# UARTAI.net
KiCad netlist of a schematic drawn in EasyEDA Pro
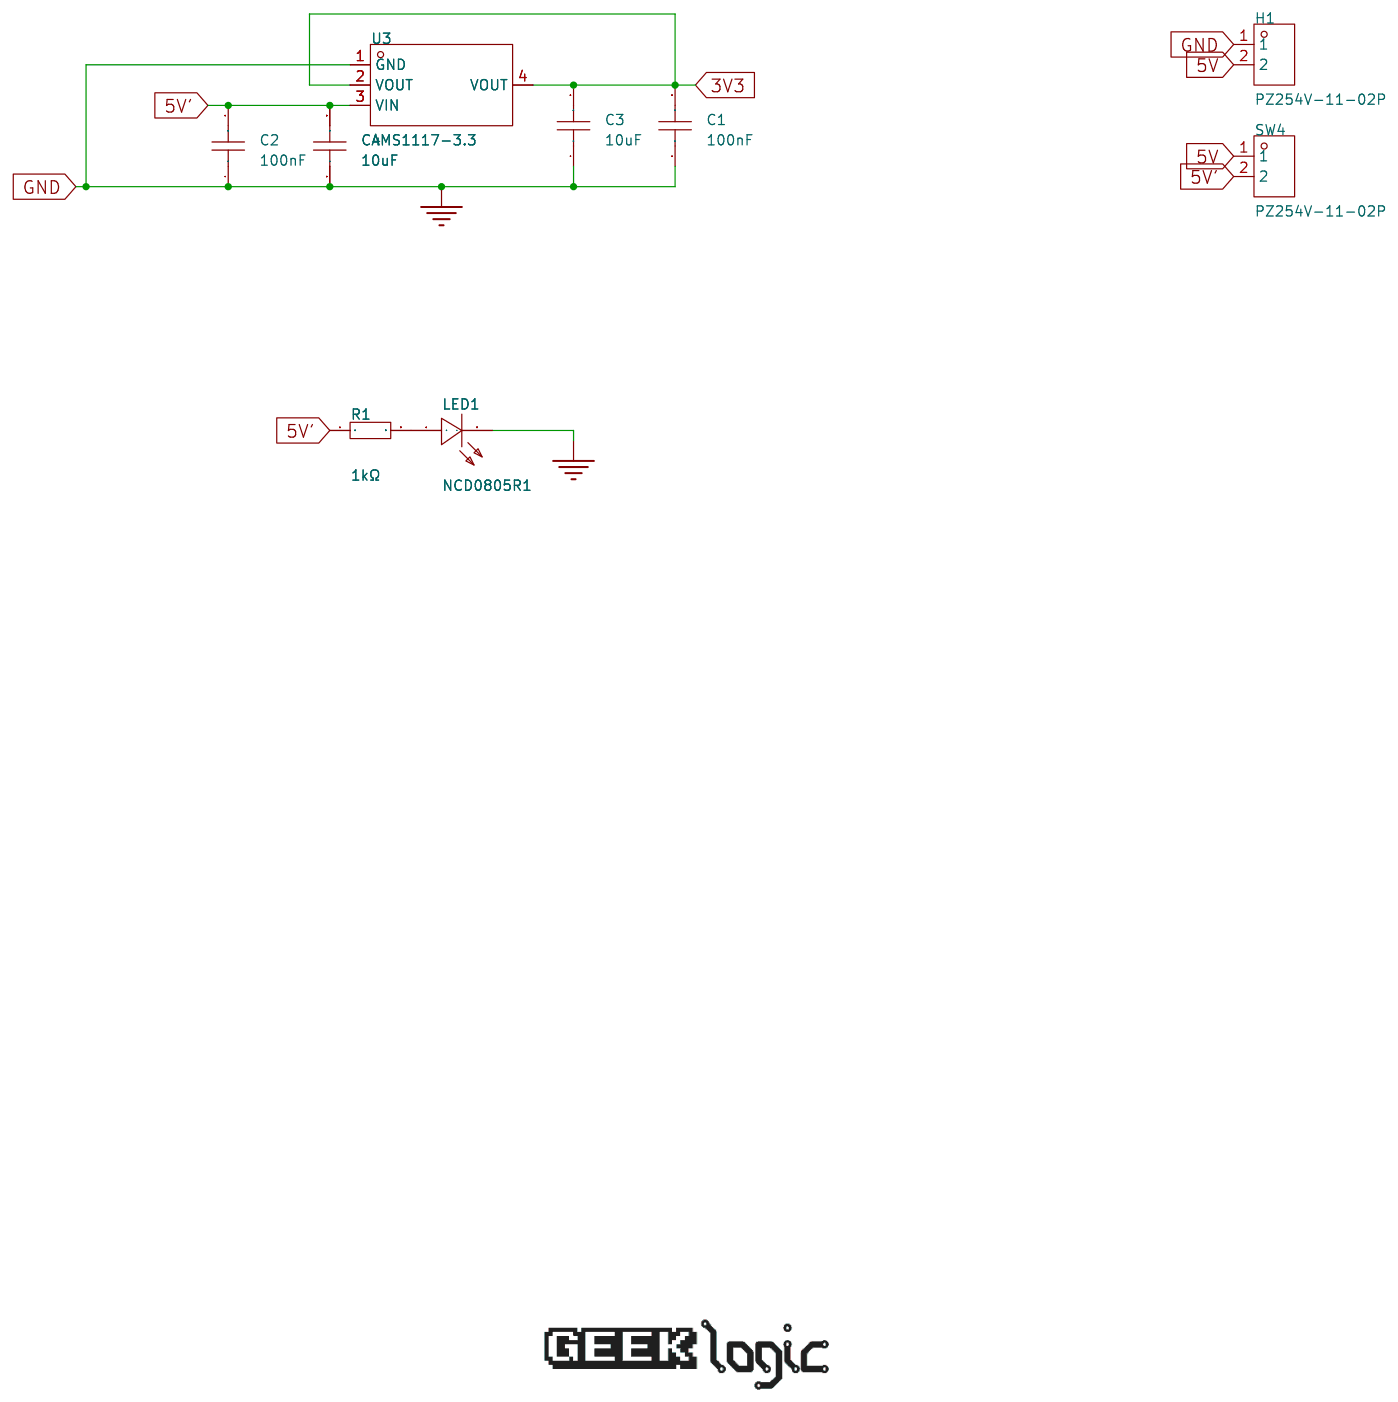
[diagram p0: Power]
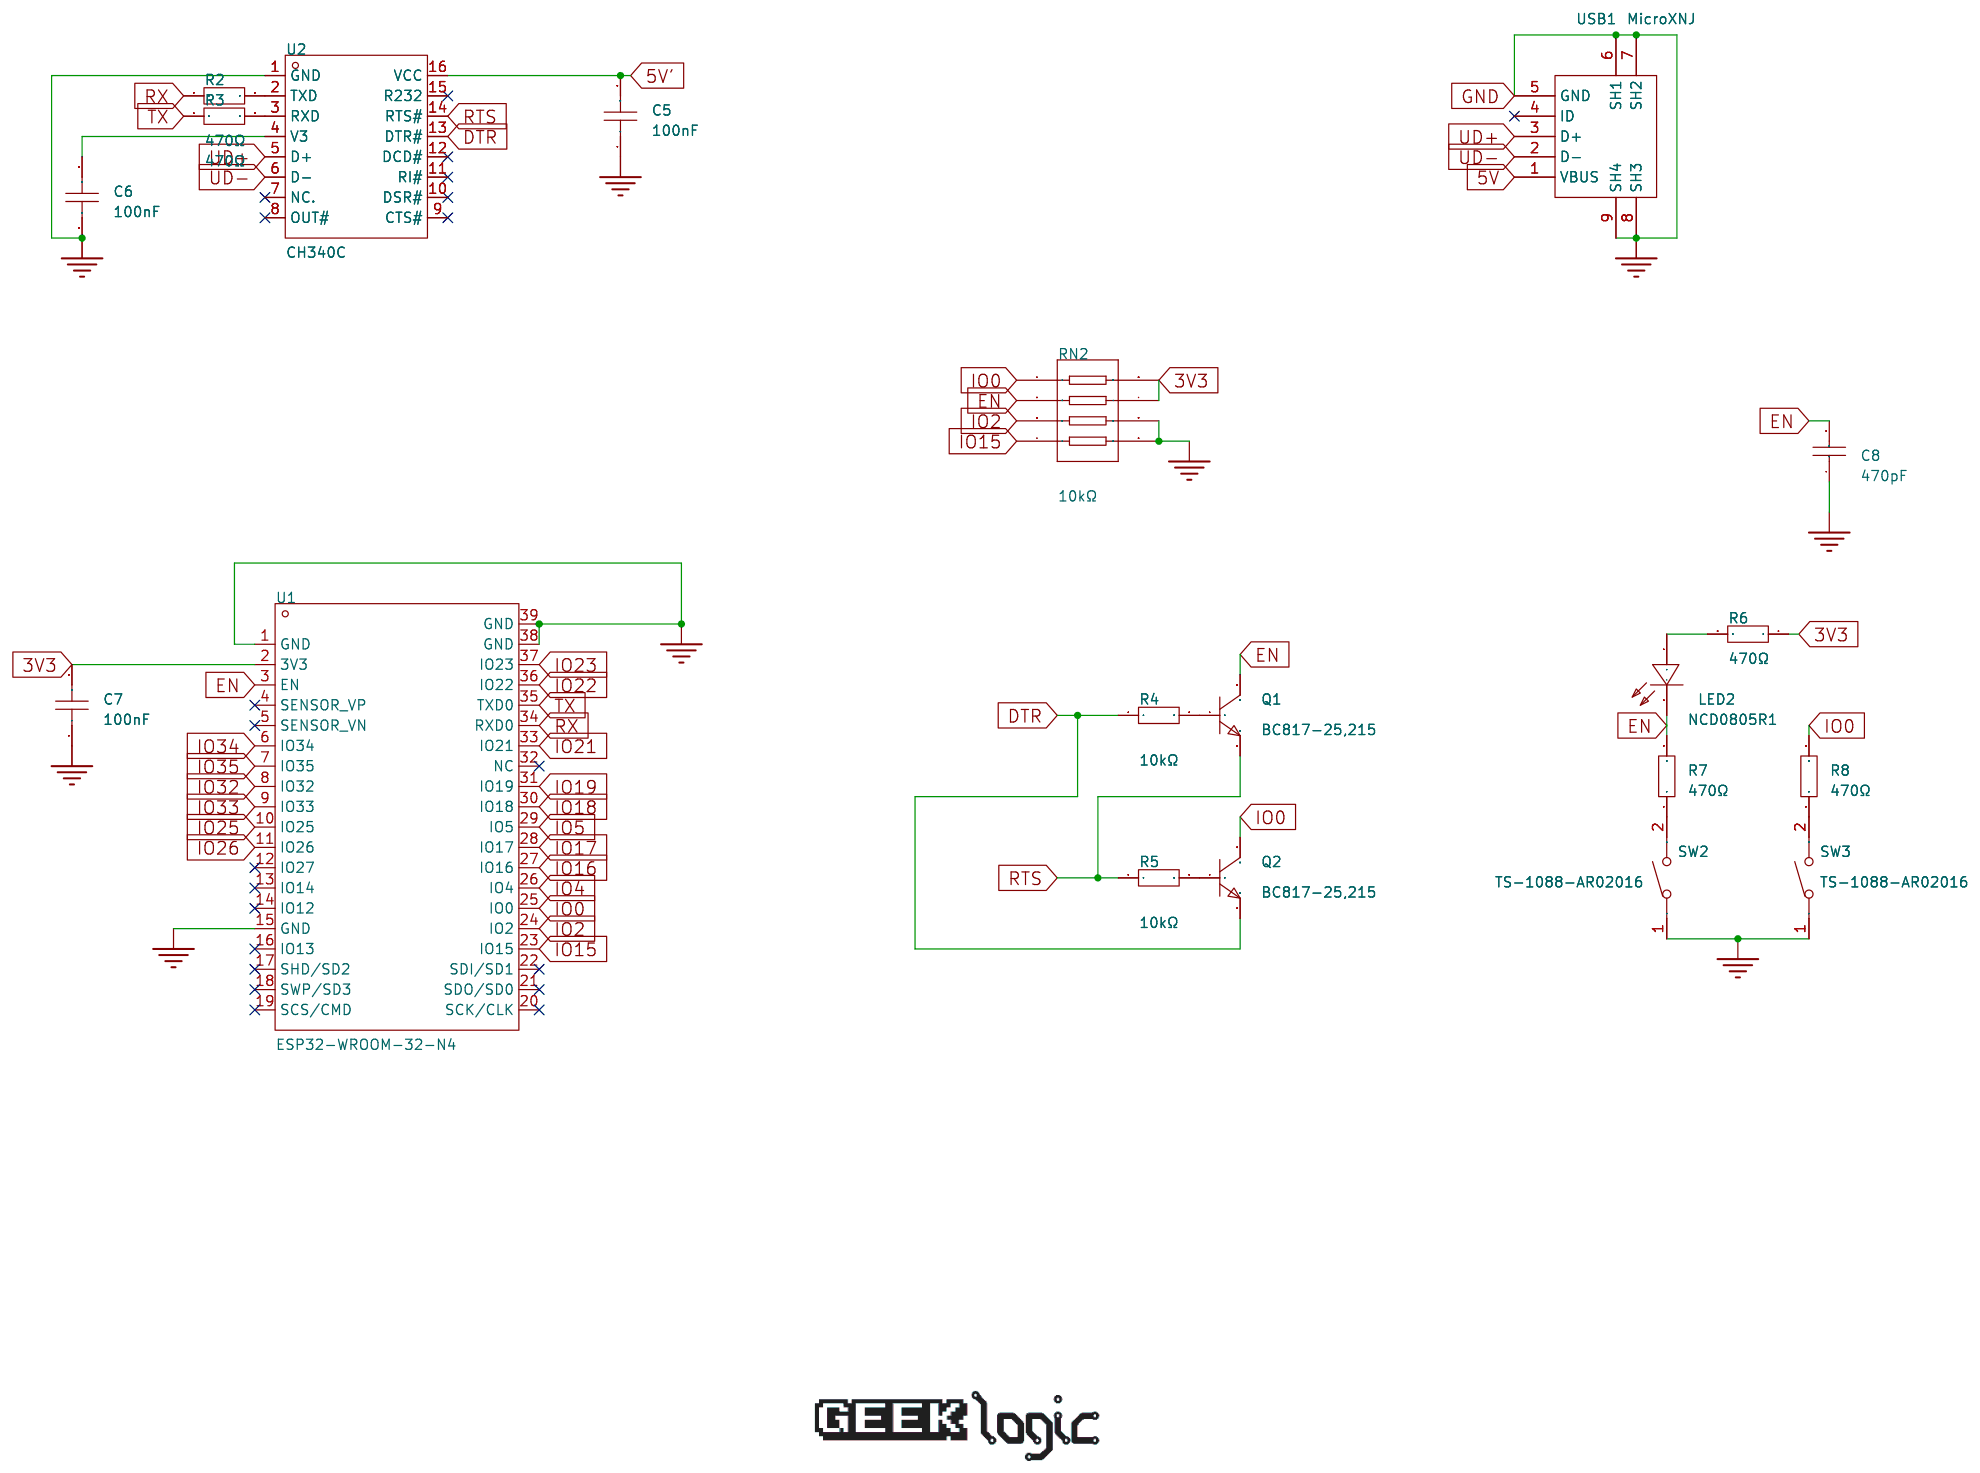
[diagram p1: MCU]
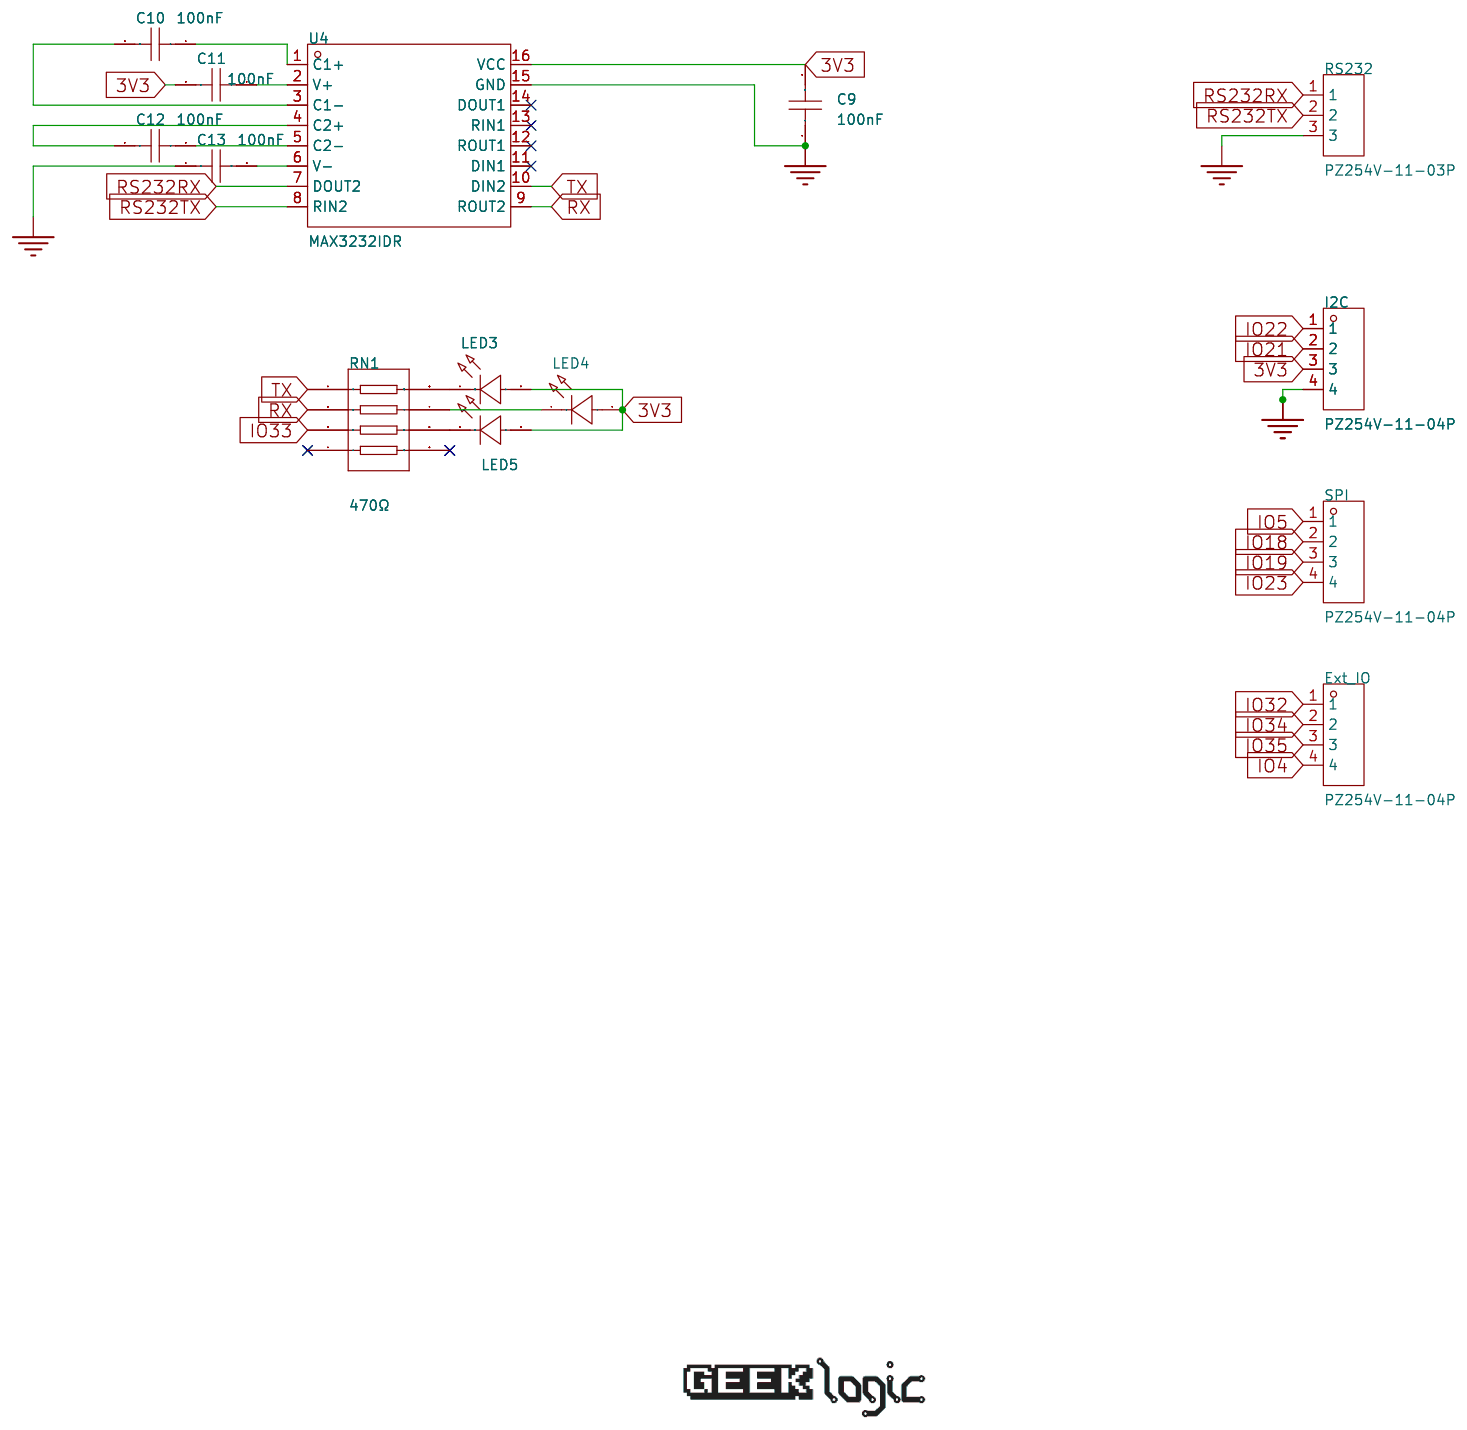
[diagram p2: RS232]

(export (version "E")
  (design (tool "Eeschema 10.0.6"))
  (components
    (comp (ref "C1")
      (value "100nF")
      (footprint "easyedapro:C0805")
      (description "容值:100nF;精度:±10%;额定电压:50V;材质(温度系数):X7R;")
      (fields
        (field (name "Manufacturer Part") "CC0805KRX7R9BB104")
        (field (name "Manufacturer") "YAGEO(国巨)")
      )
      (libsource (lib "easyedapro") (part "CC0805KRX7R9BB104"))
    )
    (comp (ref "C2")
      (value "100nF")
      (footprint "easyedapro:C0805")
      (description "容值:100nF;精度:±10%;额定电压:50V;材质(温度系数):X7R;")
      (fields
        (field (name "Manufacturer Part") "CC0805KRX7R9BB104")
        (field (name "Manufacturer") "YAGEO(国巨)")
      )
      (libsource (lib "easyedapro") (part "CC0805KRX7R9BB104"))
    )
    (comp (ref "C3")
      (value "10uF")
      (footprint "easyedapro:C0805")
      (description "容值:10uF;精度:±10%;额定电压:50V;材质(温度系数):X5R;")
      (fields
        (field (name "Manufacturer Part") "GRM21BR61H106KE43L")
        (field (name "Manufacturer") "muRata(村田)")
      )
      (libsource (lib "easyedapro") (part "GRM21BR61H106KE43L"))
    )
    (comp (ref "C4")
      (value "10uF")
      (footprint "easyedapro:C0805")
      (description "容值:10uF;精度:±10%;额定电压:50V;材质(温度系数):X5R;")
      (fields
        (field (name "Manufacturer Part") "GRM21BR61H106KE43L")
        (field (name "Manufacturer") "muRata(村田)")
      )
      (libsource (lib "easyedapro") (part "GRM21BR61H106KE43L"))
    )
    (comp (ref "H1")
      (value "PZ254V-11-02P")
      (fields (field (name "Manufacturer") "XFCN(兴飞)"))
      (libsource (lib "easyedapro") (part "PZ254V-11-02P"))
    )
    (comp (ref "LED1")
      (value "NCD0805R1")
      (footprint "easyedapro:LED0805-R-RD")
      (fields (field (name "Manufacturer") "国星光电"))
      (libsource (lib "easyedapro") (part "FC-2012HRK-620D"))
    )
    (comp (ref "R1")
      (value "1kΩ")
      (footprint "easyedapro:R0805")
      (description "电阻类型:厚膜电阻;阻值:1kΩ;精度:±1%;功率:125mW;最大工作电压:150V;温度系数:±100ppm/°C;")
      (fields
        (field (name "Manufacturer Part") "0805W8F1001T5E")
        (field (name "Manufacturer") "UNI-ROYAL(厚声)")
      )
      (libsource (lib "easyedapro") (part "0805W8F1001T5E"))
    )
    (comp (ref "SW4")
      (value "PZ254V-11-02P")
      (fields (field (name "Manufacturer") "XFCN(兴飞)"))
      (libsource (lib "easyedapro") (part "PZ254V-11-02P"))
    )
    (comp (ref "U3")
      (value "AMS1117-3.3")
      (footprint "easyedapro:SOT-223-3_L6.5-W3.4-P2.30-LS7.0-BR")
      (description "输出类型:固定;最大输入电压:-;输出电压:3.3V;最大输出电流:1A;电源纹波抑制比(PSRR):72dB@(120Hz);输出极性:正极;")
      (fields (field (name "Manufacturer") "AMS"))
      (libsource (lib "easyedapro") (part "AMS1117-3.3"))
    )
    (comp (ref "C5")
      (value "100nF")
      (footprint "easyedapro:C0805")
      (description "容值:100nF;精度:±10%;额定电压:50V;材质(温度系数):X7R;")
      (fields
        (field (name "Manufacturer Part") "CC0805KRX7R9BB104")
        (field (name "Manufacturer") "YAGEO(国巨)")
      )
      (libsource (lib "easyedapro") (part "CC0805KRX7R9BB104"))
    )
    (comp (ref "C6")
      (value "100nF")
      (footprint "easyedapro:C0805")
      (description "容值:100nF;精度:±10%;额定电压:50V;材质(温度系数):X7R;")
      (fields
        (field (name "Manufacturer Part") "CC0805KRX7R9BB104")
        (field (name "Manufacturer") "YAGEO(国巨)")
      )
      (libsource (lib "easyedapro") (part "CC0805KRX7R9BB104"))
    )
    (comp (ref "C7")
      (value "100nF")
      (footprint "easyedapro:C0805")
      (description "容值:100nF;精度:±10%;额定电压:50V;材质(温度系数):X7R;")
      (fields
        (field (name "Manufacturer Part") "CC0805KRX7R9BB104")
        (field (name "Manufacturer") "YAGEO(国巨)")
      )
      (libsource (lib "easyedapro") (part "CC0805KRX7R9BB104"))
    )
    (comp (ref "C8")
      (value "470pF")
      (footprint "easyedapro:C0805")
      (description "容值:470pF;精度:±10%;额定电压:50V;材质(温度系数):X7R;")
      (fields (field (name "Manufacturer Part") "0805B471K500NT") (field (name "Manufacturer") "FH(风华)"))
      (libsource (lib "easyedapro") (part "0805B471K500NT"))
    )
    (comp (ref "LED2")
      (value "NCD0805R1")
      (footprint "easyedapro:LED0805-R-RD")
      (fields (field (name "Manufacturer") "国星光电"))
      (libsource (lib "easyedapro") (part "FC-2012HRK-620D"))
    )
    (comp (ref "Q1")
      (value "BC817-25,215")
      (footprint "easyedapro:SOT-23-3_L2.9-W1.6-P1.90-LS2.8-BR")
      (description "晶体管类型:NPN;集电极电流(Ic):500mA;集射极击穿电压(Vceo):45V;功率(Pd):345mW;直流电流增益(hFE@Ic,Vce):160@100mA,1V;")
      (fields (field (name "Manufacturer") "Nexperia(安世)"))
      (libsource (lib "easyedapro") (part "BC817-25,215"))
    )
    (comp (ref "Q2")
      (value "BC817-25,215")
      (footprint "easyedapro:SOT-23-3_L2.9-W1.6-P1.90-LS2.8-BR")
      (description "晶体管类型:NPN;集电极电流(Ic):500mA;集射极击穿电压(Vceo):45V;功率(Pd):345mW;直流电流增益(hFE@Ic,Vce):160@100mA,1V;")
      (fields (field (name "Manufacturer") "Nexperia(安世)"))
      (libsource (lib "easyedapro") (part "BC817-25,215"))
    )
    (comp (ref "R2")
      (value "470Ω")
      (footprint "easyedapro:R0805")
      (description "电阻类型:厚膜电阻;阻值:470Ω;精度:±1%;功率:125mW;最大工作电压:150V;温度系数:±100ppm/°C;")
      (fields
        (field (name "Manufacturer Part") "0805W8F4700T5E")
        (field (name "Manufacturer") "UNI-ROYAL(厚声)")
      )
      (libsource (lib "easyedapro") (part "0805W8F4700T5E"))
    )
    (comp (ref "R3")
      (value "470Ω")
      (footprint "easyedapro:R0805")
      (description "电阻类型:厚膜电阻;阻值:470Ω;精度:±1%;功率:125mW;最大工作电压:150V;温度系数:±100ppm/°C;")
      (fields
        (field (name "Manufacturer Part") "0805W8F4700T5E")
        (field (name "Manufacturer") "UNI-ROYAL(厚声)")
      )
      (libsource (lib "easyedapro") (part "0805W8F4700T5E"))
    )
    (comp (ref "R4")
      (value "10kΩ")
      (fields
        (field (name "Manufacturer Part") "0805W8F1002T5E")
        (field (name "Manufacturer") "UNI-ROYAL(厚声)")
      )
      (libsource (lib "easyedapro") (part "0805W8F1002T5E"))
    )
    (comp (ref "R5")
      (value "10kΩ")
      (fields
        (field (name "Manufacturer Part") "0805W8F1002T5E")
        (field (name "Manufacturer") "UNI-ROYAL(厚声)")
      )
      (libsource (lib "easyedapro") (part "0805W8F1002T5E"))
    )
    (comp (ref "R6")
      (value "470Ω")
      (footprint "easyedapro:R0805")
      (description "电阻类型:厚膜电阻;阻值:470Ω;精度:±1%;功率:125mW;最大工作电压:150V;温度系数:±100ppm/°C;")
      (fields
        (field (name "Manufacturer Part") "0805W8F4700T5E")
        (field (name "Manufacturer") "UNI-ROYAL(厚声)")
      )
      (libsource (lib "easyedapro") (part "0805W8F4700T5E"))
    )
    (comp (ref "R7")
      (value "470Ω")
      (footprint "easyedapro:R0805")
      (description "电阻类型:厚膜电阻;阻值:470Ω;精度:±1%;功率:125mW;最大工作电压:150V;温度系数:±100ppm/°C;")
      (fields
        (field (name "Manufacturer Part") "0805W8F4700T5E")
        (field (name "Manufacturer") "UNI-ROYAL(厚声)")
      )
      (libsource (lib "easyedapro") (part "0805W8F4700T5E"))
    )
    (comp (ref "R8")
      (value "470Ω")
      (footprint "easyedapro:R0805")
      (description "电阻类型:厚膜电阻;阻值:470Ω;精度:±1%;功率:125mW;最大工作电压:150V;温度系数:±100ppm/°C;")
      (fields
        (field (name "Manufacturer Part") "0805W8F4700T5E")
        (field (name "Manufacturer") "UNI-ROYAL(厚声)")
      )
      (libsource (lib "easyedapro") (part "0805W8F4700T5E"))
    )
    (comp (ref "RN2")
      (value "10kΩ")
      (footprint "easyedapro:RES-ARRAY-SMD_0603-8P-L3.2-W1.6-BL")
      (description "电阻器数:4;阻值:10kΩ;精度:±5%;单个元件功率:62.5mW;温度系数:±200ppm/°C;")
      (fields
        (field (name "Manufacturer Part") "4D03WGJ0103T5E")
        (field (name "Manufacturer") "UNI-ROYAL(厚声)")
      )
      (libsource (lib "easyedapro") (part "4D03WGJ0103T5E"))
    )
    (comp (ref "SW2")
      (value "TS-1088-AR02016")
      (footprint "easyedapro:SW-SMD_L3.9-W3.0-P4.45")
      (fields (field (name "Manufacturer") "XUNPU(讯普)"))
      (libsource (lib "easyedapro") (part "TS-1088-AR02016"))
    )
    (comp (ref "SW3")
      (value "TS-1088-AR02016")
      (footprint "easyedapro:SW-SMD_L3.9-W3.0-P4.45")
      (fields (field (name "Manufacturer") "XUNPU(讯普)"))
      (libsource (lib "easyedapro") (part "TS-1088-AR02016"))
    )
    (comp (ref "U1")
      (value "ESP32-WROOM-32-N4")
      (footprint "easyedapro:WIFIM-SMD_ESP32-WROOM-32-N4")
      (description "WiFi+蓝牙4.2+双核CPU,ESP32")
      (fields (field (name "Manufacturer") "ESPRESSIF(乐鑫)"))
      (libsource (lib "easyedapro") (part "ESP32-WROOM-32"))
    )
    (comp (ref "U2")
      (value "CH340C")
      (footprint "easyedapro:SOP-16_L10.0-W3.9-P1.27-LS6.0-BL")
      (description "应用功能:收发器;接口协议:USB 2.0;数据速率:2Mbps;")
      (fields (field (name "Manufacturer") "WCH(南京沁恒)"))
      (libsource (lib "easyedapro") (part "CH340C"))
    )
    (comp (ref "USB1")
      (value "MicroXNJ")
      (footprint "easyedapro:MICRO-USB-SMD_MICROXNJ")
      (description "连接器类型:Micro-B;标准:USB 2.0;公母:母;安装方式:卧贴;触点数量:5P;端口数量:1;额定电流 - 电源:1.8A;工作温度范围:-20°C~+85°C;")
      (fields (field (name "Manufacturer") "SHOU HAN(首韩)"))
      (libsource (lib "easyedapro") (part "MICROXNJ"))
    )
    (comp (ref "C9")
      (value "100nF")
      (footprint "easyedapro:C0805")
      (description "容值:100nF;精度:±10%;额定电压:50V;材质(温度系数):X7R;")
      (fields
        (field (name "Manufacturer Part") "CC0805KRX7R9BB104")
        (field (name "Manufacturer") "YAGEO(国巨)")
      )
      (libsource (lib "easyedapro") (part "CC0805KRX7R9BB104"))
    )
    (comp (ref "C10")
      (value "100nF")
      (footprint "easyedapro:C0805")
      (description "容值:100nF;精度:±10%;额定电压:50V;材质(温度系数):X7R;")
      (fields
        (field (name "Manufacturer Part") "CC0805KRX7R9BB104")
        (field (name "Manufacturer") "YAGEO(国巨)")
      )
      (libsource (lib "easyedapro") (part "CC0805KRX7R9BB104"))
    )
    (comp (ref "C11")
      (value "100nF")
      (footprint "easyedapro:C0805")
      (description "容值:100nF;精度:±10%;额定电压:50V;材质(温度系数):X7R;")
      (fields
        (field (name "Manufacturer Part") "CC0805KRX7R9BB104")
        (field (name "Manufacturer") "YAGEO(国巨)")
      )
      (libsource (lib "easyedapro") (part "CC0805KRX7R9BB104"))
    )
    (comp (ref "C12")
      (value "100nF")
      (footprint "easyedapro:C0805")
      (description "容值:100nF;精度:±10%;额定电压:50V;材质(温度系数):X7R;")
      (fields
        (field (name "Manufacturer Part") "CC0805KRX7R9BB104")
        (field (name "Manufacturer") "YAGEO(国巨)")
      )
      (libsource (lib "easyedapro") (part "CC0805KRX7R9BB104"))
    )
    (comp (ref "C13")
      (value "100nF")
      (footprint "easyedapro:C0805")
      (description "容值:100nF;精度:±10%;额定电压:50V;材质(温度系数):X7R;")
      (fields
        (field (name "Manufacturer Part") "CC0805KRX7R9BB104")
        (field (name "Manufacturer") "YAGEO(国巨)")
      )
      (libsource (lib "easyedapro") (part "CC0805KRX7R9BB104"))
    )
    (comp (ref "Ext_IO")
      (value "PZ254V-11-04P")
      (footprint "easyedapro:HDR-TH_4P-P2.54-V-M")
      (fields (field (name "Manufacturer") "XFCN(兴飞)"))
      (libsource (lib "easyedapro") (part "PZ254V-11-04P_C2691448"))
    )
    (comp (ref "I2C")
      (value "PZ254V-11-04P")
      (footprint "easyedapro:HDR-TH_4P-P2.54-V-M")
      (fields (field (name "Manufacturer") "XFCN(兴飞)"))
      (libsource (lib "easyedapro") (part "PZ254V-11-04P_C2691448"))
    )
    (comp (ref "LED3")
      (value "SLR-342MG3F")
      (footprint "easyedapro:LED-TH_BD3.8-P2.54-RD")
      (description "灯头类型:3.1mm圆形灯头;")
      (fields (field (name "Manufacturer") "ROHM(罗姆)"))
      (libsource (lib "easyedapro") (part "SLR-342MG3F"))
    )
    (comp (ref "LED4")
      (value "SLR-342MG3F")
      (footprint "easyedapro:LED-TH_BD3.8-P2.54-RD")
      (description "灯头类型:3.1mm圆形灯头;")
      (fields (field (name "Manufacturer") "ROHM(罗姆)"))
      (libsource (lib "easyedapro") (part "SLR-342MG3F"))
    )
    (comp (ref "LED5")
      (value "SLR-342MG3F")
      (footprint "easyedapro:LED-TH_BD3.8-P2.54-RD")
      (description "灯头类型:3.1mm圆形灯头;")
      (fields (field (name "Manufacturer") "ROHM(罗姆)"))
      (libsource (lib "easyedapro") (part "SLR-342MG3F"))
    )
    (comp (ref "RN1")
      (value "470Ω")
      (footprint "easyedapro:RES-ARRAY-SMD_0603-8P-L3.2-W1.6-BL")
      (description "电阻器数:4;阻值:470Ω;精度:±5%;单个元件功率:62.5mW;温度系数:±200ppm/°C;")
      (fields
        (field (name "Manufacturer Part") "4D03WGJ0471T5E")
        (field (name "Manufacturer") "UNI-ROYAL(厚声)")
      )
      (libsource (lib "easyedapro") (part "4D03WGJ0471T5E"))
    )
    (comp (ref "RS232")
      (value "PZ254V-11-03P")
      (footprint "easyedapro:HDR-TH_3P-P2.54-V-M")
      (fields (field (name "Manufacturer") "XFCN(兴飞)"))
      (libsource (lib "easyedapro") (part "PZ254V-11-03P_C2937625"))
    )
    (comp (ref "SPI")
      (value "PZ254V-11-04P")
      (footprint "easyedapro:HDR-TH_4P-P2.54-V-M")
      (fields (field (name "Manufacturer") "XFCN(兴飞)"))
      (libsource (lib "easyedapro") (part "PZ254V-11-04P_C2691448"))
    )
    (comp (ref "U4")
      (value "MAX3232IDR")
      (footprint "easyedapro:SOIC-16_L9.9-W3.9-P1.27-LS6.0-BL")
      (description "类型:收发器;数据速率:250Kbps;")
      (fields (field (name "Manufacturer") "TI(德州仪器)"))
      (libsource (lib "easyedapro") (part "MAX3232IDR"))
    )
  )
  (nets
    (net (code "1") (name "3V3") (class "Default")
      (node (ref "C1") (pin "2") (pinfunction "2_2") (pintype "unspecified"))
      (node (ref "C11") (pin "2") (pinfunction "2_2") (pintype "unspecified"))
      (node (ref "C3") (pin "2") (pinfunction "2_2") (pintype "unspecified"))
      (node (ref "C7") (pin "2") (pinfunction "2_2") (pintype "unspecified"))
      (node (ref "C9") (pin "2") (pinfunction "2_2") (pintype "unspecified"))
      (node (ref "I2C") (pin "3") (pinfunction "3_3") (pintype "unspecified"))
      (node (ref "LED3") (pin "2") (pinfunction "A_2") (pintype "unspecified"))
      (node (ref "LED4") (pin "2") (pinfunction "A_2") (pintype "unspecified"))
      (node (ref "LED5") (pin "2") (pinfunction "A_2") (pintype "unspecified"))
      (node (ref "R6") (pin "1") (pinfunction "1_1") (pintype "input"))
      (node (ref "RN2") (pin "7") (pinfunction "7_7") (pintype "input"))
      (node (ref "RN2") (pin "8") (pinfunction "8_8") (pintype "input"))
      (node (ref "U1") (pin "2") (pinfunction "3V3_2") (pintype "unspecified"))
      (node (ref "U3") (pin "2") (pinfunction "VOUT_2") (pintype "unspecified"))
      (node (ref "U3") (pin "4") (pinfunction "VOUT_4") (pintype "unspecified"))
      (node (ref "U4") (pin "16") (pinfunction "VCC_16") (pintype "unspecified"))
    )
    (net (code "2") (name "5V") (class "Default")
      (node (ref "H1") (pin "2") (pinfunction "2_2") (pintype "unspecified"))
      (node (ref "SW4") (pin "1") (pinfunction "1_1") (pintype "unspecified"))
      (node (ref "USB1") (pin "1") (pinfunction "VBUS_1") (pintype "unspecified"))
    )
    (net (code "3") (name "5V'") (class "Default")
      (node (ref "C2") (pin "2") (pinfunction "2_2") (pintype "unspecified"))
      (node (ref "C4") (pin "2") (pinfunction "2_2") (pintype "unspecified"))
      (node (ref "C5") (pin "2") (pinfunction "2_2") (pintype "unspecified"))
      (node (ref "R1") (pin "1") (pinfunction "1_1") (pintype "input"))
      (node (ref "SW4") (pin "2") (pinfunction "2_2") (pintype "unspecified"))
      (node (ref "U2") (pin "16") (pinfunction "VCC_16") (pintype "unspecified"))
      (node (ref "U3") (pin "3") (pinfunction "VIN_3") (pintype "unspecified"))
    )
    (net (code "4") (name "DTR") (class "Default")
      (node (ref "Q2") (pin "2") (pinfunction "2_2") (pintype "input"))
      (node (ref "R4") (pin "1") (pinfunction "1_1") (pintype "input"))
      (node (ref "U2") (pin "13") (pinfunction "DTR#_13") (pintype "unspecified"))
    )
    (net (code "5") (name "EN") (class "Default")
      (node (ref "C8") (pin "2") (pinfunction "2_2") (pintype "input"))
      (node (ref "LED2") (pin "2") (pinfunction "-_2") (pintype "unspecified"))
      (node (ref "Q1") (pin "3") (pinfunction "3_3") (pintype "input"))
      (node (ref "R7") (pin "2") (pinfunction "2_2") (pintype "input"))
      (node (ref "RN2") (pin "2") (pinfunction "2_2") (pintype "input"))
      (node (ref "U1") (pin "3") (pinfunction "EN_3") (pintype "unspecified"))
    )
    (net (code "6") (name "GND") (class "Default")
      (node (ref "C1") (pin "1") (pinfunction "1_1") (pintype "unspecified"))
      (node (ref "C13") (pin "1") (pinfunction "1_1") (pintype "unspecified"))
      (node (ref "C2") (pin "1") (pinfunction "1_1") (pintype "unspecified"))
      (node (ref "C3") (pin "1") (pinfunction "1_1") (pintype "unspecified"))
      (node (ref "C4") (pin "1") (pinfunction "1_1") (pintype "unspecified"))
      (node (ref "C5") (pin "1") (pinfunction "1_1") (pintype "unspecified"))
      (node (ref "C6") (pin "1") (pinfunction "1_1") (pintype "unspecified"))
      (node (ref "C7") (pin "1") (pinfunction "1_1") (pintype "unspecified"))
      (node (ref "C8") (pin "1") (pinfunction "1_1") (pintype "input"))
      (node (ref "C9") (pin "1") (pinfunction "1_1") (pintype "unspecified"))
      (node (ref "H1") (pin "1") (pinfunction "1_1") (pintype "unspecified"))
      (node (ref "I2C") (pin "4") (pinfunction "4_4") (pintype "unspecified"))
      (node (ref "LED1") (pin "2") (pinfunction "-_2") (pintype "unspecified"))
      (node (ref "RN2") (pin "5") (pinfunction "5_5") (pintype "input"))
      (node (ref "RN2") (pin "6") (pinfunction "6_6") (pintype "input"))
      (node (ref "RS232") (pin "3") (pinfunction "3_3") (pintype "unspecified"))
      (node (ref "SW2") (pin "1") (pinfunction "1_1") (pintype "unspecified"))
      (node (ref "SW3") (pin "1") (pinfunction "1_1") (pintype "unspecified"))
      (node (ref "U1") (pin "1") (pinfunction "GND_1") (pintype "unspecified"))
      (node (ref "U1") (pin "15") (pinfunction "GND_15") (pintype "unspecified"))
      (node (ref "U1") (pin "38") (pinfunction "GND_38") (pintype "unspecified"))
      (node (ref "U1") (pin "39") (pinfunction "GND_39") (pintype "unspecified"))
      (node (ref "U2") (pin "1") (pinfunction "GND_1") (pintype "unspecified"))
      (node (ref "U3") (pin "1") (pinfunction "GND_1") (pintype "unspecified"))
      (node (ref "U4") (pin "15") (pinfunction "GND_15") (pintype "unspecified"))
      (node (ref "USB1") (pin "5") (pinfunction "GND_5") (pintype "unspecified"))
      (node (ref "USB1") (pin "6") (pinfunction "SH1_6") (pintype "unspecified"))
      (node (ref "USB1") (pin "7") (pinfunction "SH2_7") (pintype "unspecified"))
      (node (ref "USB1") (pin "8") (pinfunction "SH3_8") (pintype "unspecified"))
      (node (ref "USB1") (pin "9") (pinfunction "SH4_9") (pintype "unspecified"))
    )
    (net (code "7") (name "IO0") (class "Default")
      (node (ref "Q2") (pin "3") (pinfunction "3_3") (pintype "input"))
      (node (ref "R8") (pin "2") (pinfunction "2_2") (pintype "input"))
      (node (ref "RN2") (pin "1") (pinfunction "1_1") (pintype "input"))
      (node (ref "U1") (pin "25") (pinfunction "IO0_25") (pintype "unspecified"))
    )
    (net (code "8") (name "IO2") (class "Default")
      (node (ref "RN2") (pin "3") (pinfunction "3_3") (pintype "input"))
      (node (ref "U1") (pin "24") (pinfunction "IO2_24") (pintype "unspecified"))
    )
    (net (code "9") (name "IO4") (class "Default")
      (node (ref "Ext_IO") (pin "4") (pinfunction "4_4") (pintype "unspecified"))
      (node (ref "U1") (pin "26") (pinfunction "IO4_26") (pintype "unspecified"))
    )
    (net (code "10") (name "IO5") (class "Default")
      (node (ref "SPI") (pin "1") (pinfunction "1_1") (pintype "unspecified"))
      (node (ref "U1") (pin "29") (pinfunction "IO5_29") (pintype "unspecified"))
    )
    (net (code "11") (name "IO15") (class "Default")
      (node (ref "RN2") (pin "4") (pinfunction "4_4") (pintype "input"))
      (node (ref "U1") (pin "23") (pinfunction "IO15_23") (pintype "unspecified"))
    )
    (net (code "12") (name "IO16") (class "Default")
      (node (ref "U1") (pin "27") (pinfunction "IO16_27") (pintype "unspecified"))
    )
    (net (code "13") (name "IO17") (class "Default")
      (node (ref "U1") (pin "28") (pinfunction "IO17_28") (pintype "unspecified"))
    )
    (net (code "14") (name "IO18") (class "Default")
      (node (ref "SPI") (pin "2") (pinfunction "2_2") (pintype "unspecified"))
      (node (ref "U1") (pin "30") (pinfunction "IO18_30") (pintype "unspecified"))
    )
    (net (code "15") (name "IO19") (class "Default")
      (node (ref "SPI") (pin "3") (pinfunction "3_3") (pintype "unspecified"))
      (node (ref "U1") (pin "31") (pinfunction "IO19_31") (pintype "unspecified"))
    )
    (net (code "16") (name "IO21") (class "Default")
      (node (ref "I2C") (pin "2") (pinfunction "2_2") (pintype "unspecified"))
      (node (ref "U1") (pin "33") (pinfunction "IO21_33") (pintype "unspecified"))
    )
    (net (code "17") (name "IO22") (class "Default")
      (node (ref "I2C") (pin "1") (pinfunction "1_1") (pintype "unspecified"))
      (node (ref "U1") (pin "36") (pinfunction "IO22_36") (pintype "unspecified"))
    )
    (net (code "18") (name "IO23") (class "Default")
      (node (ref "SPI") (pin "4") (pinfunction "4_4") (pintype "unspecified"))
      (node (ref "U1") (pin "37") (pinfunction "IO23_37") (pintype "unspecified"))
    )
    (net (code "19") (name "IO25") (class "Default")
      (node (ref "U1") (pin "10") (pinfunction "IO25_10") (pintype "unspecified"))
    )
    (net (code "20") (name "IO26") (class "Default")
      (node (ref "U1") (pin "11") (pinfunction "IO26_11") (pintype "unspecified"))
    )
    (net (code "21") (name "IO32") (class "Default")
      (node (ref "Ext_IO") (pin "1") (pinfunction "1_1") (pintype "unspecified"))
      (node (ref "U1") (pin "8") (pinfunction "IO32_8") (pintype "unspecified"))
    )
    (net (code "22") (name "IO33") (class "Default")
      (node (ref "RN1") (pin "3") (pinfunction "3_3") (pintype "input"))
      (node (ref "U1") (pin "9") (pinfunction "IO33_9") (pintype "unspecified"))
    )
    (net (code "23") (name "IO34") (class "Default")
      (node (ref "Ext_IO") (pin "2") (pinfunction "2_2") (pintype "unspecified"))
      (node (ref "U1") (pin "6") (pinfunction "IO34_6") (pintype "unspecified"))
    )
    (net (code "24") (name "IO35") (class "Default")
      (node (ref "Ext_IO") (pin "3") (pinfunction "3_3") (pintype "unspecified"))
      (node (ref "U1") (pin "7") (pinfunction "IO35_7") (pintype "unspecified"))
    )
    (net (code "25") (name "Net-(LED1-+)") (class "Default")
      (node (ref "LED1") (pin "1") (pinfunction "+_1") (pintype "unspecified"))
      (node (ref "R1") (pin "2") (pinfunction "2_2") (pintype "input"))
    )
    (net (code "26") (name "Net-(LED2-+)") (class "Default")
      (node (ref "LED2") (pin "1") (pinfunction "+_1") (pintype "unspecified"))
      (node (ref "R6") (pin "2") (pinfunction "2_2") (pintype "input"))
    )
    (net (code "27") (name "Net-(LED3-C)") (class "Default")
      (node (ref "LED3") (pin "1") (pinfunction "C_1") (pintype "unspecified"))
      (node (ref "RN1") (pin "8") (pinfunction "8_8") (pintype "input"))
    )
    (net (code "28") (name "Net-(LED4-C)") (class "Default")
      (node (ref "LED4") (pin "1") (pinfunction "C_1") (pintype "unspecified"))
      (node (ref "RN1") (pin "7") (pinfunction "7_7") (pintype "input"))
    )
    (net (code "29") (name "Net-(LED5-C)") (class "Default")
      (node (ref "LED5") (pin "1") (pinfunction "C_1") (pintype "unspecified"))
      (node (ref "RN1") (pin "6") (pinfunction "6_6") (pintype "input"))
    )
    (net (code "30") (name "Net-(Q1-Pad1)") (class "Default")
      (node (ref "Q1") (pin "1") (pinfunction "1_1") (pintype "input"))
      (node (ref "R4") (pin "2") (pinfunction "2_2") (pintype "input"))
    )
    (net (code "31") (name "Net-(Q2-Pad1)") (class "Default")
      (node (ref "Q2") (pin "1") (pinfunction "1_1") (pintype "input"))
      (node (ref "R5") (pin "2") (pinfunction "2_2") (pintype "input"))
    )
    (net (code "32") (name "Net-(R7-Pad1)") (class "Default")
      (node (ref "R7") (pin "1") (pinfunction "1_1") (pintype "input"))
      (node (ref "SW2") (pin "2") (pinfunction "2_2") (pintype "unspecified"))
    )
    (net (code "33") (name "Net-(R8-Pad1)") (class "Default")
      (node (ref "R8") (pin "1") (pinfunction "1_1") (pintype "input"))
      (node (ref "SW3") (pin "2") (pinfunction "2_2") (pintype "unspecified"))
    )
    (net (code "34") (name "Net-(U2-RXD)") (class "Default")
      (node (ref "R3") (pin "2") (pinfunction "2_2") (pintype "input"))
      (node (ref "U2") (pin "3") (pinfunction "RXD_3") (pintype "unspecified"))
    )
    (net (code "35") (name "Net-(U2-TXD)") (class "Default")
      (node (ref "R2") (pin "2") (pinfunction "2_2") (pintype "input"))
      (node (ref "U2") (pin "2") (pinfunction "TXD_2") (pintype "unspecified"))
    )
    (net (code "36") (name "Net-(U2-V3)") (class "Default")
      (node (ref "C6") (pin "2") (pinfunction "2_2") (pintype "unspecified"))
      (node (ref "U2") (pin "4") (pinfunction "V3_4") (pintype "unspecified"))
    )
    (net (code "37") (name "Net-(U4-C1+)") (class "Default")
      (node (ref "C10") (pin "1") (pinfunction "1_1") (pintype "unspecified"))
      (node (ref "U4") (pin "1") (pinfunction "C1+_1") (pintype "unspecified"))
    )
    (net (code "38") (name "Net-(U4-C1-)") (class "Default")
      (node (ref "C10") (pin "2") (pinfunction "2_2") (pintype "unspecified"))
      (node (ref "U4") (pin "3") (pinfunction "C1-_3") (pintype "unspecified"))
    )
    (net (code "39") (name "Net-(U4-C2+)") (class "Default")
      (node (ref "C12") (pin "1") (pinfunction "1_1") (pintype "unspecified"))
      (node (ref "U4") (pin "4") (pinfunction "C2+_4") (pintype "unspecified"))
    )
    (net (code "40") (name "Net-(U4-C2-)") (class "Default")
      (node (ref "C12") (pin "2") (pinfunction "2_2") (pintype "unspecified"))
      (node (ref "U4") (pin "5") (pinfunction "C2-_5") (pintype "unspecified"))
    )
    (net (code "41") (name "Net-(U4-V+)") (class "Default")
      (node (ref "C11") (pin "1") (pinfunction "1_1") (pintype "unspecified"))
      (node (ref "U4") (pin "2") (pinfunction "V+_2") (pintype "unspecified"))
    )
    (net (code "42") (name "Net-(U4-V-)") (class "Default")
      (node (ref "C13") (pin "2") (pinfunction "2_2") (pintype "unspecified"))
      (node (ref "U4") (pin "6") (pinfunction "V-_6") (pintype "unspecified"))
    )
    (net (code "43") (name "RS232RX") (class "Default")
      (node (ref "RS232") (pin "1") (pinfunction "1_1") (pintype "unspecified"))
      (node (ref "U4") (pin "7") (pinfunction "DOUT2_7") (pintype "unspecified"))
    )
    (net (code "44") (name "RS232TX") (class "Default")
      (node (ref "RS232") (pin "2") (pinfunction "2_2") (pintype "unspecified"))
      (node (ref "U4") (pin "8") (pinfunction "RIN2_8") (pintype "unspecified"))
    )
    (net (code "45") (name "RTS") (class "Default")
      (node (ref "Q1") (pin "2") (pinfunction "2_2") (pintype "input"))
      (node (ref "R5") (pin "1") (pinfunction "1_1") (pintype "input"))
      (node (ref "U2") (pin "14") (pinfunction "RTS#_14") (pintype "unspecified"))
    )
    (net (code "46") (name "RX") (class "Default")
      (node (ref "R2") (pin "1") (pinfunction "1_1") (pintype "input"))
      (node (ref "RN1") (pin "2") (pinfunction "2_2") (pintype "input"))
      (node (ref "U1") (pin "34") (pinfunction "RXD0_34") (pintype "unspecified"))
      (node (ref "U4") (pin "9") (pinfunction "ROUT2_9") (pintype "unspecified"))
    )
    (net (code "47") (name "TX") (class "Default")
      (node (ref "R3") (pin "1") (pinfunction "1_1") (pintype "input"))
      (node (ref "RN1") (pin "1") (pinfunction "1_1") (pintype "input"))
      (node (ref "U1") (pin "35") (pinfunction "TXD0_35") (pintype "unspecified"))
      (node (ref "U4") (pin "10") (pinfunction "DIN2_10") (pintype "unspecified"))
    )
    (net (code "48") (name "UD+") (class "Default")
      (node (ref "U2") (pin "5") (pinfunction "D+_5") (pintype "unspecified"))
      (node (ref "USB1") (pin "3") (pinfunction "D+_3") (pintype "unspecified"))
    )
    (net (code "49") (name "UD-") (class "Default")
      (node (ref "U2") (pin "6") (pinfunction "D-_6") (pintype "unspecified"))
      (node (ref "USB1") (pin "2") (pinfunction "D-_2") (pintype "unspecified"))
    )
    (net (code "50") (name "unconnected-(RN1-Pad4)") (class "Default")
      (node (ref "RN1") (pin "4") (pinfunction "4_4") (pintype "input+no_connect"))
    )
    (net (code "51") (name "unconnected-(RN1-Pad5)") (class "Default")
      (node (ref "RN1") (pin "5") (pinfunction "5_5") (pintype "input+no_connect"))
    )
    (net (code "52") (name "unconnected-(U1-IO12-Pad14)") (class "Default")
      (node (ref "U1") (pin "14") (pinfunction "IO12_14") (pintype "unspecified+no_connect"))
    )
    (net (code "53") (name "unconnected-(U1-IO13-Pad16)") (class "Default")
      (node (ref "U1") (pin "16") (pinfunction "IO13_16") (pintype "unspecified+no_connect"))
    )
    (net (code "54") (name "unconnected-(U1-IO14-Pad13)") (class "Default")
      (node (ref "U1") (pin "13") (pinfunction "IO14_13") (pintype "unspecified+no_connect"))
    )
    (net (code "55") (name "unconnected-(U1-IO27-Pad12)") (class "Default")
      (node (ref "U1") (pin "12") (pinfunction "IO27_12") (pintype "unspecified+no_connect"))
    )
    (net (code "56") (name "unconnected-(U1-NC-Pad32)") (class "Default")
      (node (ref "U1") (pin "32") (pinfunction "NC_32") (pintype "unspecified+no_connect"))
    )
    (net (code "57") (name "unconnected-(U1-SCK{slash}CLK-Pad20)") (class "Default")
      (node (ref "U1") (pin "20") (pinfunction "SCK/CLK_20") (pintype "unspecified+no_connect"))
    )
    (net (code "58") (name "unconnected-(U1-SCS{slash}CMD-Pad19)") (class "Default")
      (node (ref "U1") (pin "19") (pinfunction "SCS/CMD_19") (pintype "unspecified+no_connect"))
    )
    (net (code "59") (name "unconnected-(U1-SDI{slash}SD1-Pad22)") (class "Default")
      (node (ref "U1") (pin "22") (pinfunction "SDI/SD1_22") (pintype "unspecified+no_connect"))
    )
    (net (code "60") (name "unconnected-(U1-SDO{slash}SD0-Pad21)") (class "Default")
      (node (ref "U1") (pin "21") (pinfunction "SDO/SD0_21") (pintype "unspecified+no_connect"))
    )
    (net (code "61") (name "unconnected-(U1-SENSOR_VN-Pad5)") (class "Default")
      (node (ref "U1") (pin "5") (pinfunction "SENSOR_VN_5") (pintype "unspecified+no_connect"))
    )
    (net (code "62") (name "unconnected-(U1-SENSOR_VP-Pad4)") (class "Default")
      (node (ref "U1") (pin "4") (pinfunction "SENSOR_VP_4") (pintype "unspecified+no_connect"))
    )
    (net (code "63") (name "unconnected-(U1-SHD{slash}SD2-Pad17)") (class "Default")
      (node (ref "U1") (pin "17") (pinfunction "SHD/SD2_17") (pintype "unspecified+no_connect"))
    )
    (net (code "64") (name "unconnected-(U1-SWP{slash}SD3-Pad18)") (class "Default")
      (node (ref "U1") (pin "18") (pinfunction "SWP/SD3_18") (pintype "unspecified+no_connect"))
    )
    (net (code "65") (name "unconnected-(U2-CTS#-Pad9)") (class "Default")
      (node (ref "U2") (pin "9") (pinfunction "CTS#_9") (pintype "unspecified+no_connect"))
    )
    (net (code "66") (name "unconnected-(U2-DCD#-Pad12)") (class "Default")
      (node (ref "U2") (pin "12") (pinfunction "DCD#_12") (pintype "unspecified+no_connect"))
    )
    (net (code "67") (name "unconnected-(U2-DSR#-Pad10)") (class "Default")
      (node (ref "U2") (pin "10") (pinfunction "DSR#_10") (pintype "unspecified+no_connect"))
    )
    (net (code "68") (name "unconnected-(U2-NC.-Pad7)") (class "Default")
      (node (ref "U2") (pin "7") (pinfunction "NC._7") (pintype "unspecified+no_connect"))
    )
    (net (code "69") (name "unconnected-(U2-OUT#-Pad8)") (class "Default")
      (node (ref "U2") (pin "8") (pinfunction "OUT#_8") (pintype "unspecified+no_connect"))
    )
    (net (code "70") (name "unconnected-(U2-R232-Pad15)") (class "Default")
      (node (ref "U2") (pin "15") (pinfunction "R232_15") (pintype "unspecified+no_connect"))
    )
    (net (code "71") (name "unconnected-(U2-RI#-Pad11)") (class "Default")
      (node (ref "U2") (pin "11") (pinfunction "RI#_11") (pintype "unspecified+no_connect"))
    )
    (net (code "72") (name "unconnected-(U4-DIN1-Pad11)") (class "Default")
      (node (ref "U4") (pin "11") (pinfunction "DIN1_11") (pintype "unspecified+no_connect"))
    )
    (net (code "73") (name "unconnected-(U4-DOUT1-Pad14)") (class "Default")
      (node (ref "U4") (pin "14") (pinfunction "DOUT1_14") (pintype "unspecified+no_connect"))
    )
    (net (code "74") (name "unconnected-(U4-RIN1-Pad13)") (class "Default")
      (node (ref "U4") (pin "13") (pinfunction "RIN1_13") (pintype "unspecified+no_connect"))
    )
    (net (code "75") (name "unconnected-(U4-ROUT1-Pad12)") (class "Default")
      (node (ref "U4") (pin "12") (pinfunction "ROUT1_12") (pintype "unspecified+no_connect"))
    )
    (net (code "76") (name "unconnected-(USB1-ID-Pad4)") (class "Default")
      (node (ref "USB1") (pin "4") (pinfunction "ID_4") (pintype "unspecified+no_connect"))
    )
  )
)
